# de10_out_board.net
KiCad netlist of a schematic drawn in EAGLE
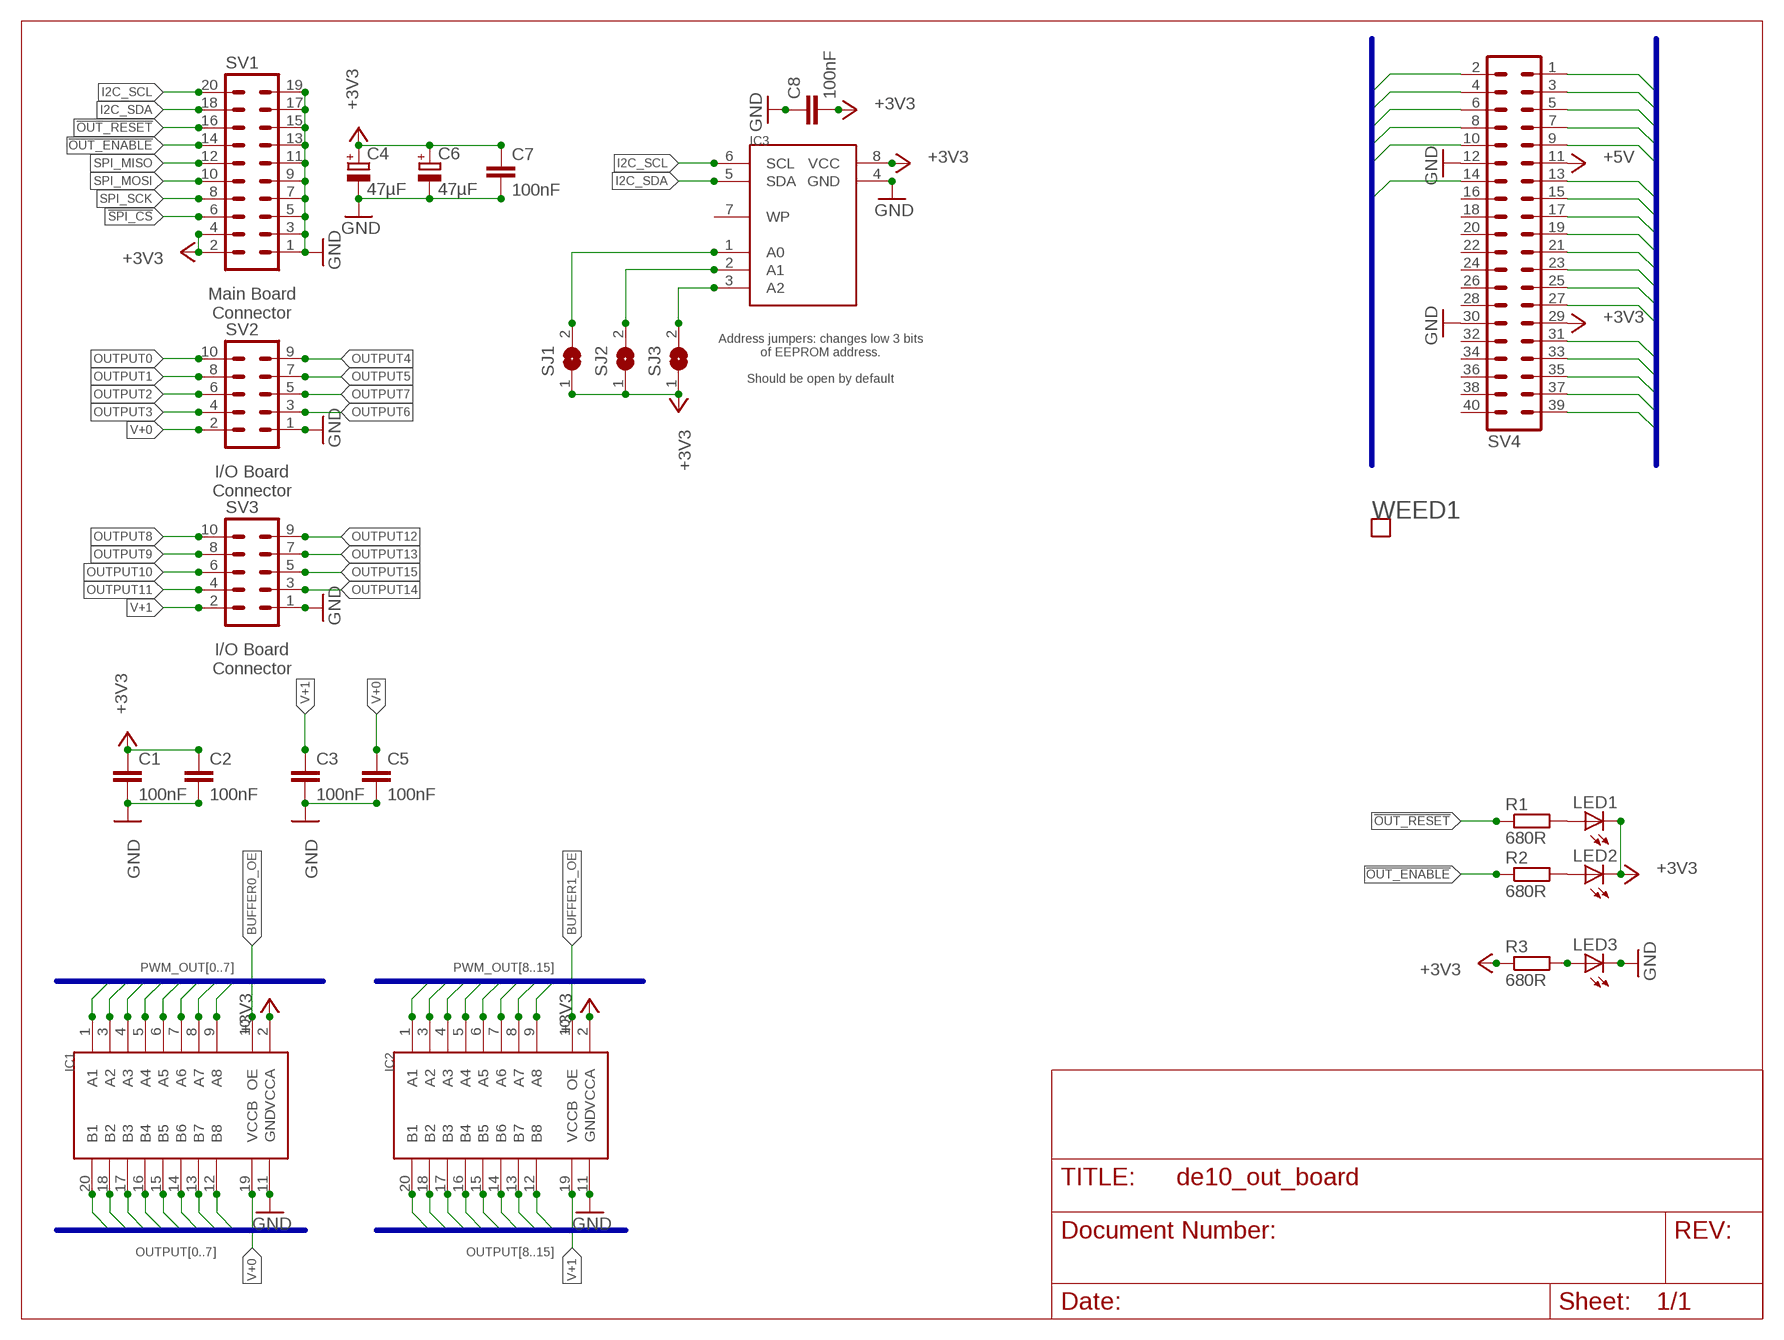
[diagram p0: schematic, sheet 1]

(export (version "E")
  (design (tool "Eeschema 10.0.6"))
  (components
    (comp (ref "C1")
      (value "100nF")
      (footprint "eagle-import:C0805")
      (libsource (lib "eagle-import") (part "C-EUC0805"))
    )
    (comp (ref "C2")
      (value "100nF")
      (footprint "eagle-import:C0805")
      (libsource (lib "eagle-import") (part "C-EUC0805"))
    )
    (comp (ref "C3")
      (value "100nF")
      (footprint "eagle-import:C0805")
      (libsource (lib "eagle-import") (part "C-EUC0805"))
    )
    (comp (ref "C4")
      (value "47µF")
      (footprint "eagle-import:CT7343")
      (libsource (lib "eagle-import") (part "CPOL-EUCT7343"))
    )
    (comp (ref "C5")
      (value "100nF")
      (footprint "eagle-import:C0805")
      (libsource (lib "eagle-import") (part "C-EUC0805"))
    )
    (comp (ref "C6")
      (value "47µF")
      (footprint "eagle-import:CT7343")
      (libsource (lib "eagle-import") (part "CPOL-EUCT7343"))
    )
    (comp (ref "C7")
      (value "100nF")
      (footprint "eagle-import:C0805")
      (libsource (lib "eagle-import") (part "C-EUC0805"))
    )
    (comp (ref "C8")
      (value "100nF")
      (footprint "eagle-import:C0805")
      (libsource (lib "eagle-import") (part "C-EUC0805"))
    )
    (comp (ref "IC1")
      (value "TXB0108TSSOP20")
      (footprint "eagle-import:TSSOP20")
      (libsource (lib "eagle-import") (part "TXB0108TSSOP20"))
    )
    (comp (ref "IC2")
      (value "TXB0108TSSOP20")
      (footprint "eagle-import:TSSOP20")
      (libsource (lib "eagle-import") (part "TXB0108TSSOP20"))
    )
    (comp (ref "IC3")
      (value "AT24C02DSOIC-8")
      (footprint "eagle-import:SOIC8")
      (libsource (lib "eagle-import") (part "AT24C02DSOIC-8"))
    )
    (comp (ref "LED1")
      (value "LEDCHIPLED_1206")
      (footprint "eagle-import:CHIPLED_1206")
      (libsource (lib "eagle-import") (part "LEDCHIPLED_1206"))
    )
    (comp (ref "LED2")
      (value "LEDCHIPLED_1206")
      (footprint "eagle-import:CHIPLED_1206")
      (libsource (lib "eagle-import") (part "LEDCHIPLED_1206"))
    )
    (comp (ref "LED3")
      (value "LEDCHIPLED_1206")
      (footprint "eagle-import:CHIPLED_1206")
      (libsource (lib "eagle-import") (part "LEDCHIPLED_1206"))
    )
    (comp (ref "R1")
      (value "680R")
      (footprint "eagle-import:M0805")
      (libsource (lib "eagle-import") (part "R-EU_M0805"))
    )
    (comp (ref "R2")
      (value "680R")
      (footprint "eagle-import:M0805")
      (libsource (lib "eagle-import") (part "R-EU_M0805"))
    )
    (comp (ref "R3")
      (value "680R")
      (footprint "eagle-import:M0805")
      (libsource (lib "eagle-import") (part "R-EU_M0805"))
    )
    (comp (ref "SJ1") (value "SJ") (footprint "eagle-import:SJ") (libsource (lib "eagle-import") (part "SJ")))
    (comp (ref "SJ2") (value "SJ") (footprint "eagle-import:SJ") (libsource (lib "eagle-import") (part "SJ")))
    (comp (ref "SJ3") (value "SJ") (footprint "eagle-import:SJ") (libsource (lib "eagle-import") (part "SJ")))
    (comp (ref "SV1")
      (value "MA10-2")
      (footprint "eagle-import:MA10-2")
      (libsource (lib "eagle-import") (part "MA10-2"))
    )
    (comp (ref "SV2")
      (value "MA05-2")
      (footprint "eagle-import:MA05-2")
      (libsource (lib "eagle-import") (part "MA05-2"))
    )
    (comp (ref "SV3")
      (value "MA05-2")
      (footprint "eagle-import:MA05-2")
      (libsource (lib "eagle-import") (part "MA05-2"))
    )
    (comp (ref "SV4")
      (value "MA20-2")
      (footprint "eagle-import:MA20-2")
      (fields (field (name "SPICEPREFIX") "X"))
      (libsource (lib "eagle-import") (part "MA20-2"))
    )
    (comp (ref "WEED1")
      (value "WEED")
      (footprint "eagle-import:DOINK")
      (libsource (lib "eagle-import") (part "WEED"))
    )
  )
  (nets
    (net (code "1") (name "+3V3") (class "Default")
      (node (ref "C1") (pin "1") (pinfunction "1_1") (pintype "passive"))
      (node (ref "C2") (pin "1") (pinfunction "1_1") (pintype "passive"))
      (node (ref "C4") (pin "+") (pinfunction "+_+") (pintype "passive"))
      (node (ref "C6") (pin "+") (pinfunction "+_+") (pintype "passive"))
      (node (ref "C7") (pin "1") (pinfunction "1_1") (pintype "passive"))
      (node (ref "C8") (pin "2") (pinfunction "2_2") (pintype "passive"))
      (node (ref "IC1") (pin "2") (pinfunction "VCCA_2") (pintype "bidirectional"))
      (node (ref "IC2") (pin "2") (pinfunction "VCCA_2") (pintype "bidirectional"))
      (node (ref "IC3") (pin "8") (pinfunction "VCC_8") (pintype "power_in"))
      (node (ref "LED1") (pin "C") (pinfunction "C_C") (pintype "passive"))
      (node (ref "LED2") (pin "C") (pinfunction "C_C") (pintype "passive"))
      (node (ref "R3") (pin "1") (pinfunction "1_1") (pintype "passive"))
      (node (ref "SJ1") (pin "1") (pinfunction "1_1") (pintype "passive"))
      (node (ref "SJ2") (pin "1") (pinfunction "1_1") (pintype "passive"))
      (node (ref "SJ3") (pin "1") (pinfunction "1_1") (pintype "passive"))
      (node (ref "SV1") (pin "2") (pinfunction "2_2") (pintype "passive"))
      (node (ref "SV1") (pin "4") (pinfunction "4_4") (pintype "passive"))
      (node (ref "SV4") (pin "29") (pinfunction "29_29") (pintype "passive"))
    )
    (net (code "2") (name "+5V") (class "Default")
      (node (ref "SV4") (pin "11") (pinfunction "11_11") (pintype "passive"))
    )
    (net (code "5") (name "/PWM_OUT0") (class "Default")
      (node (ref "IC1") (pin "9") (pinfunction "A8_9") (pintype "bidirectional"))
      (node (ref "SV4") (pin "23") (pinfunction "23_23") (pintype "passive"))
    )
    (net (code "6") (name "/PWM_OUT1") (class "Default")
      (node (ref "IC1") (pin "8") (pinfunction "A7_8") (pintype "bidirectional"))
      (node (ref "SV4") (pin "25") (pinfunction "25_25") (pintype "passive"))
    )
    (net (code "7") (name "/PWM_OUT2") (class "Default")
      (node (ref "IC1") (pin "7") (pinfunction "A6_7") (pintype "bidirectional"))
      (node (ref "SV4") (pin "27") (pinfunction "27_27") (pintype "passive"))
    )
    (net (code "8") (name "/PWM_OUT3") (class "Default")
      (node (ref "IC1") (pin "6") (pinfunction "A5_6") (pintype "bidirectional"))
      (node (ref "SV4") (pin "31") (pinfunction "31_31") (pintype "passive"))
    )
    (net (code "9") (name "/PWM_OUT4") (class "Default")
      (node (ref "IC1") (pin "5") (pinfunction "A4_5") (pintype "bidirectional"))
      (node (ref "SV4") (pin "33") (pinfunction "33_33") (pintype "passive"))
    )
    (net (code "10") (name "/PWM_OUT5") (class "Default")
      (node (ref "IC1") (pin "4") (pinfunction "A3_4") (pintype "bidirectional"))
      (node (ref "SV4") (pin "35") (pinfunction "35_35") (pintype "passive"))
    )
    (net (code "11") (name "/PWM_OUT6") (class "Default")
      (node (ref "IC1") (pin "3") (pinfunction "A2_3") (pintype "bidirectional"))
      (node (ref "SV4") (pin "37") (pinfunction "37_37") (pintype "passive"))
    )
    (net (code "12") (name "/PWM_OUT7") (class "Default")
      (node (ref "IC1") (pin "1") (pinfunction "A1_1") (pintype "bidirectional"))
      (node (ref "SV4") (pin "39") (pinfunction "39_39") (pintype "passive"))
    )
    (net (code "13") (name "/PWM_OUT8") (class "Default")
      (node (ref "IC2") (pin "9") (pinfunction "A8_9") (pintype "bidirectional"))
      (node (ref "SV4") (pin "3") (pinfunction "3_3") (pintype "passive"))
    )
    (net (code "14") (name "/PWM_OUT9") (class "Default")
      (node (ref "IC2") (pin "8") (pinfunction "A7_8") (pintype "bidirectional"))
      (node (ref "SV4") (pin "5") (pinfunction "5_5") (pintype "passive"))
    )
    (net (code "15") (name "/PWM_OUT10") (class "Default")
      (node (ref "IC2") (pin "7") (pinfunction "A6_7") (pintype "bidirectional"))
      (node (ref "SV4") (pin "7") (pinfunction "7_7") (pintype "passive"))
    )
    (net (code "16") (name "/PWM_OUT11") (class "Default")
      (node (ref "IC2") (pin "6") (pinfunction "A5_6") (pintype "bidirectional"))
      (node (ref "SV4") (pin "9") (pinfunction "9_9") (pintype "passive"))
    )
    (net (code "17") (name "/PWM_OUT12") (class "Default")
      (node (ref "IC2") (pin "5") (pinfunction "A4_5") (pintype "bidirectional"))
      (node (ref "SV4") (pin "13") (pinfunction "13_13") (pintype "passive"))
    )
    (net (code "18") (name "/PWM_OUT13") (class "Default")
      (node (ref "IC2") (pin "4") (pinfunction "A3_4") (pintype "bidirectional"))
      (node (ref "SV4") (pin "15") (pinfunction "15_15") (pintype "passive"))
    )
    (net (code "19") (name "/PWM_OUT14") (class "Default")
      (node (ref "IC2") (pin "3") (pinfunction "A2_3") (pintype "bidirectional"))
      (node (ref "SV4") (pin "17") (pinfunction "17_17") (pintype "passive"))
    )
    (net (code "20") (name "/PWM_OUT15") (class "Default")
      (node (ref "IC2") (pin "1") (pinfunction "A1_1") (pintype "bidirectional"))
      (node (ref "SV4") (pin "19") (pinfunction "19_19") (pintype "passive"))
    )
    (net (code "24") (name "/~{OUT_ENABLE}") (class "Default")
      (node (ref "R2") (pin "1") (pinfunction "1_1") (pintype "passive"))
      (node (ref "SV1") (pin "14") (pinfunction "14_14") (pintype "passive"))
      (node (ref "SV4") (pin "10") (pinfunction "10_10") (pintype "passive"))
    )
    (net (code "25") (name "/~{OUT_RESET}") (class "Default")
      (node (ref "R1") (pin "1") (pinfunction "1_1") (pintype "passive"))
      (node (ref "SV1") (pin "16") (pinfunction "16_16") (pintype "passive"))
      (node (ref "SV4") (pin "14") (pinfunction "14_14") (pintype "passive"))
    )
    (net (code "26") (name "/~{SPI_CS}") (class "Default")
      (node (ref "SV1") (pin "6") (pinfunction "6_6") (pintype "passive"))
      (node (ref "SV4") (pin "2") (pinfunction "2_2") (pintype "passive"))
    )
    (net (code "27") (name "BUFFER0_OE") (class "Default")
      (node (ref "IC1") (pin "10") (pinfunction "OE_10") (pintype "bidirectional"))
      (node (ref "SV4") (pin "21") (pinfunction "21_21") (pintype "passive"))
    )
    (net (code "28") (name "BUFFER1_OE") (class "Default")
      (node (ref "IC2") (pin "10") (pinfunction "OE_10") (pintype "bidirectional"))
      (node (ref "SV4") (pin "1") (pinfunction "1_1") (pintype "passive"))
    )
    (net (code "29") (name "GND") (class "Default")
      (node (ref "C1") (pin "2") (pinfunction "2_2") (pintype "passive"))
      (node (ref "C2") (pin "2") (pinfunction "2_2") (pintype "passive"))
      (node (ref "C3") (pin "2") (pinfunction "2_2") (pintype "passive"))
      (node (ref "C4") (pin "-") (pinfunction "-_-") (pintype "passive"))
      (node (ref "C5") (pin "2") (pinfunction "2_2") (pintype "passive"))
      (node (ref "C6") (pin "-") (pinfunction "-_-") (pintype "passive"))
      (node (ref "C7") (pin "2") (pinfunction "2_2") (pintype "passive"))
      (node (ref "C8") (pin "1") (pinfunction "1_1") (pintype "passive"))
      (node (ref "IC1") (pin "11") (pinfunction "GND_11") (pintype "bidirectional"))
      (node (ref "IC2") (pin "11") (pinfunction "GND_11") (pintype "bidirectional"))
      (node (ref "IC3") (pin "4") (pinfunction "GND_4") (pintype "power_in"))
      (node (ref "LED3") (pin "C") (pinfunction "C_C") (pintype "passive"))
      (node (ref "SV1") (pin "1") (pinfunction "1_1") (pintype "passive"))
      (node (ref "SV1") (pin "11") (pinfunction "11_11") (pintype "passive"))
      (node (ref "SV1") (pin "13") (pinfunction "13_13") (pintype "passive"))
      (node (ref "SV1") (pin "15") (pinfunction "15_15") (pintype "passive"))
      (node (ref "SV1") (pin "17") (pinfunction "17_17") (pintype "passive"))
      (node (ref "SV1") (pin "19") (pinfunction "19_19") (pintype "passive"))
      (node (ref "SV1") (pin "3") (pinfunction "3_3") (pintype "passive"))
      (node (ref "SV1") (pin "5") (pinfunction "5_5") (pintype "passive"))
      (node (ref "SV1") (pin "7") (pinfunction "7_7") (pintype "passive"))
      (node (ref "SV1") (pin "9") (pinfunction "9_9") (pintype "passive"))
      (node (ref "SV2") (pin "1") (pinfunction "1_1") (pintype "passive"))
      (node (ref "SV3") (pin "1") (pinfunction "1_1") (pintype "passive"))
      (node (ref "SV4") (pin "12") (pinfunction "12_12") (pintype "passive"))
      (node (ref "SV4") (pin "30") (pinfunction "30_30") (pintype "passive"))
    )
    (net (code "30") (name "I2C_SCL") (class "Default")
      (node (ref "IC3") (pin "6") (pinfunction "SCL_6") (pintype "bidirectional"))
      (node (ref "SV1") (pin "20") (pinfunction "20_20") (pintype "passive"))
    )
    (net (code "31") (name "I2C_SDA") (class "Default")
      (node (ref "IC3") (pin "5") (pinfunction "SDA_5") (pintype "bidirectional"))
      (node (ref "SV1") (pin "18") (pinfunction "18_18") (pintype "passive"))
    )
    (net (code "32") (name "Net-(IC3-A0)") (class "Default")
      (node (ref "IC3") (pin "1") (pinfunction "A0_1") (pintype "bidirectional"))
      (node (ref "SJ1") (pin "2") (pinfunction "2_2") (pintype "passive"))
    )
    (net (code "33") (name "Net-(IC3-A1)") (class "Default")
      (node (ref "IC3") (pin "2") (pinfunction "A1_2") (pintype "bidirectional"))
      (node (ref "SJ2") (pin "2") (pinfunction "2_2") (pintype "passive"))
    )
    (net (code "34") (name "Net-(IC3-A2)") (class "Default")
      (node (ref "IC3") (pin "3") (pinfunction "A2_3") (pintype "bidirectional"))
      (node (ref "SJ3") (pin "2") (pinfunction "2_2") (pintype "passive"))
    )
    (net (code "35") (name "Net-(LED1-PadA)") (class "Default")
      (node (ref "LED1") (pin "A") (pinfunction "A_A") (pintype "passive"))
      (node (ref "R1") (pin "2") (pinfunction "2_2") (pintype "passive"))
    )
    (net (code "36") (name "Net-(LED2-PadA)") (class "Default")
      (node (ref "LED2") (pin "A") (pinfunction "A_A") (pintype "passive"))
      (node (ref "R2") (pin "2") (pinfunction "2_2") (pintype "passive"))
    )
    (net (code "37") (name "Net-(LED3-PadA)") (class "Default")
      (node (ref "LED3") (pin "A") (pinfunction "A_A") (pintype "passive"))
      (node (ref "R3") (pin "2") (pinfunction "2_2") (pintype "passive"))
    )
    (net (code "38") (name "OUTPUT0") (class "Default")
      (node (ref "IC1") (pin "20") (pinfunction "B1_20") (pintype "bidirectional"))
      (node (ref "SV2") (pin "10") (pinfunction "10_10") (pintype "passive"))
    )
    (net (code "39") (name "OUTPUT1") (class "Default")
      (node (ref "IC1") (pin "18") (pinfunction "B2_18") (pintype "bidirectional"))
      (node (ref "SV2") (pin "8") (pinfunction "8_8") (pintype "passive"))
    )
    (net (code "40") (name "OUTPUT2") (class "Default")
      (node (ref "IC1") (pin "17") (pinfunction "B3_17") (pintype "bidirectional"))
      (node (ref "SV2") (pin "6") (pinfunction "6_6") (pintype "passive"))
    )
    (net (code "41") (name "OUTPUT3") (class "Default")
      (node (ref "IC1") (pin "16") (pinfunction "B4_16") (pintype "bidirectional"))
      (node (ref "SV2") (pin "4") (pinfunction "4_4") (pintype "passive"))
    )
    (net (code "42") (name "OUTPUT4") (class "Default")
      (node (ref "IC1") (pin "15") (pinfunction "B5_15") (pintype "bidirectional"))
      (node (ref "SV2") (pin "9") (pinfunction "9_9") (pintype "passive"))
    )
    (net (code "43") (name "OUTPUT5") (class "Default")
      (node (ref "IC1") (pin "14") (pinfunction "B6_14") (pintype "bidirectional"))
      (node (ref "SV2") (pin "7") (pinfunction "7_7") (pintype "passive"))
    )
    (net (code "44") (name "OUTPUT6") (class "Default")
      (node (ref "IC1") (pin "13") (pinfunction "B7_13") (pintype "bidirectional"))
      (node (ref "SV2") (pin "3") (pinfunction "3_3") (pintype "passive"))
    )
    (net (code "45") (name "OUTPUT7") (class "Default")
      (node (ref "IC1") (pin "12") (pinfunction "B8_12") (pintype "bidirectional"))
      (node (ref "SV2") (pin "5") (pinfunction "5_5") (pintype "passive"))
    )
    (net (code "46") (name "OUTPUT8") (class "Default")
      (node (ref "IC2") (pin "20") (pinfunction "B1_20") (pintype "bidirectional"))
      (node (ref "SV3") (pin "10") (pinfunction "10_10") (pintype "passive"))
    )
    (net (code "47") (name "OUTPUT9") (class "Default")
      (node (ref "IC2") (pin "18") (pinfunction "B2_18") (pintype "bidirectional"))
      (node (ref "SV3") (pin "8") (pinfunction "8_8") (pintype "passive"))
    )
    (net (code "48") (name "OUTPUT10") (class "Default")
      (node (ref "IC2") (pin "17") (pinfunction "B3_17") (pintype "bidirectional"))
      (node (ref "SV3") (pin "6") (pinfunction "6_6") (pintype "passive"))
    )
    (net (code "49") (name "OUTPUT11") (class "Default")
      (node (ref "IC2") (pin "16") (pinfunction "B4_16") (pintype "bidirectional"))
      (node (ref "SV3") (pin "4") (pinfunction "4_4") (pintype "passive"))
    )
    (net (code "50") (name "OUTPUT12") (class "Default")
      (node (ref "IC2") (pin "15") (pinfunction "B5_15") (pintype "bidirectional"))
      (node (ref "SV3") (pin "9") (pinfunction "9_9") (pintype "passive"))
    )
    (net (code "51") (name "OUTPUT13") (class "Default")
      (node (ref "IC2") (pin "14") (pinfunction "B6_14") (pintype "bidirectional"))
      (node (ref "SV3") (pin "7") (pinfunction "7_7") (pintype "passive"))
    )
    (net (code "52") (name "OUTPUT14") (class "Default")
      (node (ref "IC2") (pin "13") (pinfunction "B7_13") (pintype "bidirectional"))
      (node (ref "SV3") (pin "3") (pinfunction "3_3") (pintype "passive"))
    )
    (net (code "53") (name "OUTPUT15") (class "Default")
      (node (ref "IC2") (pin "12") (pinfunction "B8_12") (pintype "bidirectional"))
      (node (ref "SV3") (pin "5") (pinfunction "5_5") (pintype "passive"))
    )
    (net (code "54") (name "SPI_MISO") (class "Default")
      (node (ref "SV1") (pin "12") (pinfunction "12_12") (pintype "passive"))
      (node (ref "SV4") (pin "8") (pinfunction "8_8") (pintype "passive"))
    )
    (net (code "55") (name "SPI_MOSI") (class "Default")
      (node (ref "SV1") (pin "10") (pinfunction "10_10") (pintype "passive"))
      (node (ref "SV4") (pin "6") (pinfunction "6_6") (pintype "passive"))
    )
    (net (code "56") (name "SPI_SCK") (class "Default")
      (node (ref "SV1") (pin "8") (pinfunction "8_8") (pintype "passive"))
      (node (ref "SV4") (pin "4") (pinfunction "4_4") (pintype "passive"))
    )
    (net (code "57") (name "V+0") (class "Default")
      (node (ref "C5") (pin "1") (pinfunction "1_1") (pintype "passive"))
      (node (ref "IC1") (pin "19") (pinfunction "VCCB_19") (pintype "bidirectional"))
      (node (ref "SV2") (pin "2") (pinfunction "2_2") (pintype "passive"))
    )
    (net (code "58") (name "V+1") (class "Default")
      (node (ref "C3") (pin "1") (pinfunction "1_1") (pintype "passive"))
      (node (ref "IC2") (pin "19") (pinfunction "VCCB_19") (pintype "bidirectional"))
      (node (ref "SV3") (pin "2") (pinfunction "2_2") (pintype "passive"))
    )
    (net (code "59") (name "unconnected-(IC3-WP-Pad7)") (class "Default")
      (node (ref "IC3") (pin "7") (pinfunction "WP_7") (pintype "bidirectional"))
    )
    (net (code "60") (name "unconnected-(SV4-Pad16)") (class "Default")
      (node (ref "SV4") (pin "16") (pinfunction "16_16") (pintype "passive"))
    )
    (net (code "61") (name "unconnected-(SV4-Pad18)") (class "Default")
      (node (ref "SV4") (pin "18") (pinfunction "18_18") (pintype "passive"))
    )
    (net (code "62") (name "unconnected-(SV4-Pad20)") (class "Default")
      (node (ref "SV4") (pin "20") (pinfunction "20_20") (pintype "passive"))
    )
    (net (code "63") (name "unconnected-(SV4-Pad22)") (class "Default")
      (node (ref "SV4") (pin "22") (pinfunction "22_22") (pintype "passive"))
    )
    (net (code "64") (name "unconnected-(SV4-Pad24)") (class "Default")
      (node (ref "SV4") (pin "24") (pinfunction "24_24") (pintype "passive"))
    )
    (net (code "65") (name "unconnected-(SV4-Pad26)") (class "Default")
      (node (ref "SV4") (pin "26") (pinfunction "26_26") (pintype "passive"))
    )
    (net (code "66") (name "unconnected-(SV4-Pad28)") (class "Default")
      (node (ref "SV4") (pin "28") (pinfunction "28_28") (pintype "passive"))
    )
    (net (code "67") (name "unconnected-(SV4-Pad32)") (class "Default")
      (node (ref "SV4") (pin "32") (pinfunction "32_32") (pintype "passive"))
    )
    (net (code "68") (name "unconnected-(SV4-Pad34)") (class "Default")
      (node (ref "SV4") (pin "34") (pinfunction "34_34") (pintype "passive"))
    )
    (net (code "69") (name "unconnected-(SV4-Pad36)") (class "Default")
      (node (ref "SV4") (pin "36") (pinfunction "36_36") (pintype "passive"))
    )
    (net (code "70") (name "unconnected-(SV4-Pad38)") (class "Default")
      (node (ref "SV4") (pin "38") (pinfunction "38_38") (pintype "passive"))
    )
    (net (code "71") (name "unconnected-(SV4-Pad40)") (class "Default")
      (node (ref "SV4") (pin "40") (pinfunction "40_40") (pintype "passive"))
    )
  )
)
